# TOP.net
KiCad netlist of a schematic drawn in Altium Designer
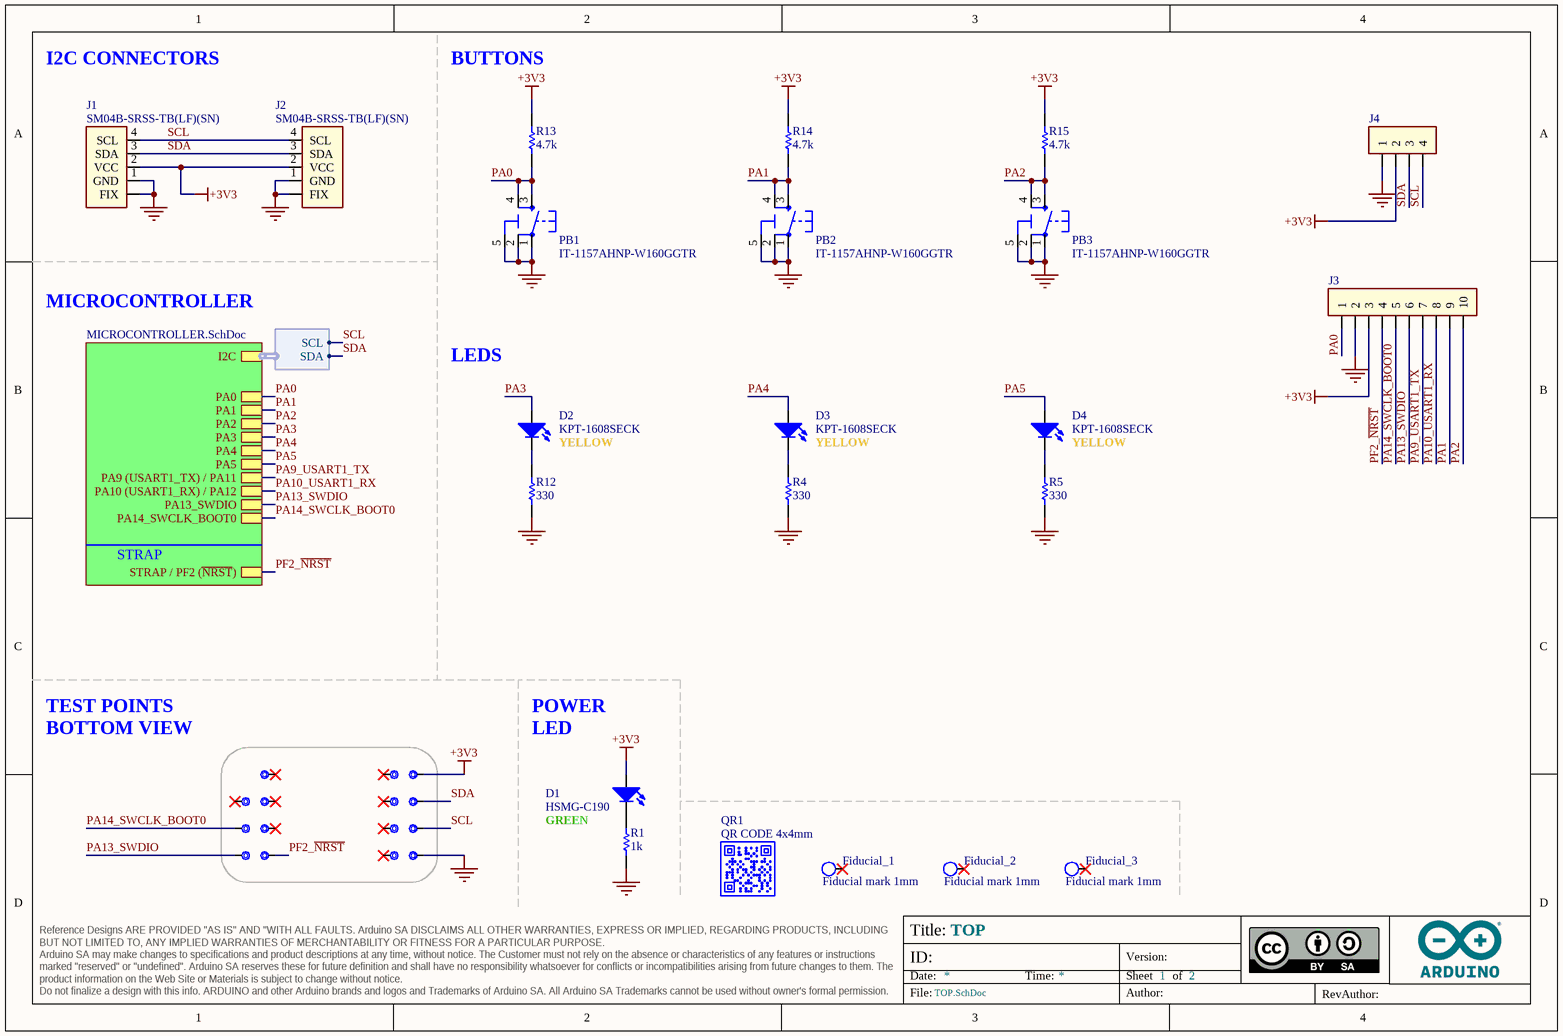
[diagram p0: TOP.SchDoc]

(export (version "E")
  (design (tool "Eeschema 10.0.6"))
  (components
    (comp (ref "3V3")
      (value "Test point 1.00mm")
      (footprint "TP-1.00MM")
      (fields (field (name "MANUFACTURER") "This is not a component"))
      (libsource (lib "Clean") (part "TESTPOINT"))
    )
    (comp (ref "D1")
      (value "HSMG-C190")
      (footprint "LEDC1608X80N-AK")
      (description "LED SMD 0603 GREEN/568 15mcd 120^")
      (fields (field (name "MANUFACTURER") "Broadcom"))
      (libsource (lib "Clean") (part "LED"))
    )
    (comp (ref "D2")
      (value "KPT-1608SECK")
      (footprint "LEDC1608X80N-AK")
      (description "LED SMD 0603 ORANGE601 250mcd 120^")
      (fields (field (name "MANUFACTURER") "Kingbright"))
      (libsource (lib "Clean") (part "LED"))
    )
    (comp (ref "D3")
      (value "KPT-1608SECK")
      (footprint "LEDC1608X80N-AK")
      (description "LED SMD 0603 ORANGE601 250mcd 120^")
      (fields (field (name "MANUFACTURER") "Kingbright"))
      (libsource (lib "Clean") (part "LED"))
    )
    (comp (ref "D4")
      (value "KPT-1608SECK")
      (footprint "LEDC1608X80N-AK")
      (description "LED SMD 0603 ORANGE601 250mcd 120^")
      (fields (field (name "MANUFACTURER") "Kingbright"))
      (libsource (lib "Clean") (part "LED"))
    )
    (comp (ref "Fiducial_1")
      (value "Fiducial mark 1mm")
      (footprint "Fiducial mark 1mm-Footprint-1")
      (description "Fiducial mark 1mm clearance 2mm")
      (libsource (lib "Clean") (part "Fiducial mark 1mm"))
    )
    (comp (ref "Fiducial_2")
      (value "Fiducial mark 1mm")
      (footprint "Fiducial mark 1mm-Footprint-1")
      (description "Fiducial mark 1mm clearance 2mm")
      (libsource (lib "Clean") (part "Fiducial mark 1mm"))
    )
    (comp (ref "Fiducial_3")
      (value "Fiducial mark 1mm")
      (footprint "Fiducial mark 1mm-Footprint-1")
      (description "Fiducial mark 1mm clearance 2mm")
      (libsource (lib "Clean") (part "Fiducial mark 1mm"))
    )
    (comp (ref "GND")
      (value "Test point 1.00mm")
      (footprint "TP-1.00MM")
      (fields (field (name "MANUFACTURER") "This is not a component"))
      (libsource (lib "Clean") (part "TESTPOINT"))
    )
    (comp (ref "J1")
      (value "SM04B-SRSS-TB(LF)(SN)")
      (footprint "SM04B-SRSS-TB(LF)(SN)-Footprint-1")
      (description "CONN JST 4POS SIDE 1MM TIN QWIIC")
      (fields (field (name "MANUFACTURER") "JST"))
      (libsource (lib "") (part "SM04B-SRSS-TB(LF)(SN)_1"))
    )
    (comp (ref "J2")
      (value "SM04B-SRSS-TB(LF)(SN)")
      (footprint "SM04B-SRSS-TB(LF)(SN)-Footprint-1")
      (description "CONN JST 4POS SIDE 1MM TIN QWIIC")
      (fields (field (name "MANUFACTURER") "JST"))
      (libsource (lib "Clean") (part "SM04B-SRSS-TB(LF)(SN)"))
    )
    (comp (ref "J3")
      (value "HEADER TH 2.54mm VERT. 1x010POS")
      (footprint "PIN HEADER 2.54mm VERT. 1x10POS")
      (libsource (lib "Clean") (part "PIN HEADER 2.54mm VERT. 1x10POS"))
    )
    (comp (ref "J4")
      (value "HEADER TH 2.54mm VERT. 1x004POS")
      (footprint "PIN HEADER 2.54mm VERT. 1x4POS-Footprint-1")
      (libsource (lib "Clean") (part "PIN HEADER 2.54mm VERT. 1x4POS"))
    )
    (comp (ref "NRST")
      (value "Test point 1.00mm")
      (footprint "TP-1.00MM")
      (fields (field (name "MANUFACTURER") "This is not a component"))
      (libsource (lib "Clean") (part "TESTPOINT"))
    )
    (comp (ref "PA6")
      (value "Test point 1.00mm")
      (footprint "TP-1.00MM")
      (fields (field (name "MANUFACTURER") "This is not a component"))
      (libsource (lib "Clean") (part "TESTPOINT"))
    )
    (comp (ref "PA7")
      (value "Test point 1.00mm")
      (footprint "TP-1.00MM")
      (fields (field (name "MANUFACTURER") "This is not a component"))
      (libsource (lib "Clean") (part "TESTPOINT"))
    )
    (comp (ref "PB1")
      (value "IT-1157AHNP-W160GGTR")
      (footprint "TS42")
      (description "PUSHBUTTON SMD 6x6 5 PINS")
      (fields (field (name "MANUFACTURER") "Switronic"))
      (libsource (lib "Clean") (part "IT-1157AHNP-W160GGTR"))
    )
    (comp (ref "PB2")
      (value "IT-1157AHNP-W160GGTR")
      (footprint "TS42")
      (description "PUSHBUTTON SMD 6x6 5 PINS")
      (fields (field (name "MANUFACTURER") "Switronic"))
      (libsource (lib "Clean") (part "IT-1157AHNP-W160GGTR"))
    )
    (comp (ref "PB3")
      (value "IT-1157AHNP-W160GGTR")
      (footprint "TS42")
      (description "PUSHBUTTON SMD 6x6 5 PINS")
      (fields (field (name "MANUFACTURER") "Switronic"))
      (libsource (lib "Clean") (part "IT-1157AHNP-W160GGTR"))
    )
    (comp (ref "PC14")
      (value "Test point 1.00mm")
      (footprint "TP-1.00MM")
      (fields (field (name "MANUFACTURER") "This is not a component"))
      (libsource (lib "Clean") (part "TESTPOINT"))
    )
    (comp (ref "PC15")
      (value "Test point 1.00mm")
      (footprint "TP-1.00MM")
      (fields (field (name "MANUFACTURER") "This is not a component"))
      (libsource (lib "Clean") (part "TESTPOINT"))
    )
    (comp (ref "QR1")
      (value "QR CODE 4x4mm")
      (footprint "QR CODE 4x4mm")
      (description "QR CODE 4x4mm on layer 34 (This is not a component)")
      (fields (field (name "PART NUMBER") "This is not a component"))
      (libsource (lib "Clean") (part "QR CODE 4x4mm"))
    )
    (comp (ref "R1")
      (value "1k")
      (footprint "RES-0402")
      (description "RES CHIP 0402 1k 1% 1/16W")
      (fields (field (name "PART NUMBER") "CRCW04021K00FKEDC") (field (name "TOLERANCE") "1%"))
      (libsource (lib "Clean") (part "RES"))
    )
    (comp (ref "R4")
      (value "330")
      (footprint "RES-0402")
      (description "RES CHIP 0402 330R 5% 1/16W")
      (fields (field (name "PART NUMBER") "CRCW0402330RJNED") (field (name "TOLERANCE") "5%"))
      (libsource (lib "Clean") (part "RES"))
    )
    (comp (ref "R5")
      (value "330")
      (footprint "RES-0402")
      (description "RES CHIP 0402 330R 5% 1/16W")
      (fields (field (name "PART NUMBER") "CRCW0402330RJNED") (field (name "TOLERANCE") "5%"))
      (libsource (lib "Clean") (part "RES"))
    )
    (comp (ref "R12")
      (value "330")
      (footprint "RES-0402")
      (description "RES CHIP 0402 330R 5% 1/16W")
      (fields (field (name "PART NUMBER") "CRCW0402330RJNED") (field (name "TOLERANCE") "5%"))
      (libsource (lib "Clean") (part "RES"))
    )
    (comp (ref "R13")
      (value "4.7k")
      (footprint "RES-0402")
      (description "RES CHIP 0402 4k7 1% 1/16W")
      (fields (field (name "PART NUMBER") "RC0402FR-074K7L") (field (name "TOLERANCE") "1%"))
      (libsource (lib "Clean") (part "RES"))
    )
    (comp (ref "R14")
      (value "4.7k")
      (footprint "RES-0402")
      (description "RES CHIP 0402 4k7 1% 1/16W")
      (fields (field (name "PART NUMBER") "RC0402FR-074K7L") (field (name "TOLERANCE") "1%"))
      (libsource (lib "Clean") (part "RES"))
    )
    (comp (ref "R15")
      (value "4.7k")
      (footprint "RES-0402")
      (description "RES CHIP 0402 4k7 1% 1/16W")
      (fields (field (name "PART NUMBER") "RC0402FR-074K7L") (field (name "TOLERANCE") "1%"))
      (libsource (lib "Clean") (part "RES"))
    )
    (comp (ref "SCL")
      (value "Test point 1.00mm")
      (footprint "TP-1.00MM")
      (fields (field (name "MANUFACTURER") "This is not a component"))
      (libsource (lib "Clean") (part "TESTPOINT"))
    )
    (comp (ref "SDA")
      (value "Test point 1.00mm")
      (footprint "TP-1.00MM")
      (fields (field (name "MANUFACTURER") "This is not a component"))
      (libsource (lib "Clean") (part "TESTPOINT"))
    )
    (comp (ref "SWCLK")
      (value "Test point 1.00mm")
      (footprint "TP-1.00MM")
      (fields (field (name "MANUFACTURER") "This is not a component"))
      (libsource (lib "Clean") (part "TESTPOINT"))
    )
    (comp (ref "SWDIO")
      (value "Test point 1.00mm")
      (footprint "TP-1.00MM")
      (fields (field (name "MANUFACTURER") "This is not a component"))
      (libsource (lib "Clean") (part "TESTPOINT"))
    )
    (comp (ref "TP9")
      (value "Test point 1.00mm")
      (footprint "TP-1.00MM")
      (fields (field (name "MANUFACTURER") "This is not a component"))
      (libsource (lib "Clean") (part "TESTPOINT"))
    )
    (comp (ref "TP10")
      (value "Test point 1.00mm")
      (footprint "TP-1.00MM")
      (fields (field (name "MANUFACTURER") "This is not a component"))
      (libsource (lib "Clean") (part "TESTPOINT"))
    )
    (comp (ref "TP11")
      (value "Test point 1.00mm")
      (footprint "TP-1.00MM")
      (fields (field (name "MANUFACTURER") "This is not a component"))
      (libsource (lib "Clean") (part "TESTPOINT"))
    )
    (comp (ref "TP12")
      (value "Test point 1.00mm")
      (footprint "TP-1.00MM")
      (fields (field (name "MANUFACTURER") "This is not a component"))
      (libsource (lib "Clean") (part "TESTPOINT"))
    )
  )
  (nets
    (net (code "2") (name "+3V3") (class "Default")
      (node (ref "3V3") (pin "X") (pinfunction "X_X") (pintype "passive"))
      (node (ref "D1") (pin "A") (pinfunction "A_A") (pintype "passive"))
      (node (ref "J1") (pin "2") (pinfunction "VCC_2") (pintype "passive"))
      (node (ref "J2") (pin "2") (pinfunction "VCC_2") (pintype "passive"))
      (node (ref "J3") (pin "3") (pinfunction "3_3") (pintype "passive"))
      (node (ref "J4") (pin "2") (pinfunction "2_2") (pintype "passive"))
      (node (ref "R13") (pin "2") (pinfunction "2_2") (pintype "passive"))
      (node (ref "R14") (pin "2") (pinfunction "2_2") (pintype "passive"))
      (node (ref "R15") (pin "2") (pinfunction "2_2") (pintype "passive"))
    )
    (net (code "3") (name "/PA0") (class "Default")
      (node (ref "J3") (pin "1") (pinfunction "1_1") (pintype "passive"))
      (node (ref "PB1") (pin "3") (pinfunction "3_3") (pintype "passive"))
      (node (ref "PB1") (pin "4") (pinfunction "4_4") (pintype "passive"))
      (node (ref "R13") (pin "1") (pinfunction "1_1") (pintype "passive"))
    )
    (net (code "4") (name "/PA1") (class "Default")
      (node (ref "J3") (pin "9") (pinfunction "9_9") (pintype "passive"))
      (node (ref "PB2") (pin "3") (pinfunction "3_3") (pintype "passive"))
      (node (ref "PB2") (pin "4") (pinfunction "4_4") (pintype "passive"))
      (node (ref "R14") (pin "1") (pinfunction "1_1") (pintype "passive"))
    )
    (net (code "5") (name "/PA2") (class "Default")
      (node (ref "J3") (pin "10") (pinfunction "10_10") (pintype "passive"))
      (node (ref "PB3") (pin "3") (pinfunction "3_3") (pintype "passive"))
      (node (ref "PB3") (pin "4") (pinfunction "4_4") (pintype "passive"))
      (node (ref "R15") (pin "1") (pinfunction "1_1") (pintype "passive"))
    )
    (net (code "6") (name "/PA3") (class "Default")
      (node (ref "D2") (pin "A") (pinfunction "A_A") (pintype "passive"))
    )
    (net (code "7") (name "/PA4") (class "Default")
      (node (ref "D3") (pin "A") (pinfunction "A_A") (pintype "passive"))
    )
    (net (code "8") (name "/PA5") (class "Default")
      (node (ref "D4") (pin "A") (pinfunction "A_A") (pintype "passive"))
    )
    (net (code "9") (name "/PA9_USART1_TX") (class "Default")
      (node (ref "J3") (pin "7") (pinfunction "7_7") (pintype "passive"))
    )
    (net (code "10") (name "/PA10_USART1_RX") (class "Default")
      (node (ref "J3") (pin "8") (pinfunction "8_8") (pintype "passive"))
    )
    (net (code "11") (name "/PA13_SWDIO") (class "Default")
      (node (ref "J3") (pin "6") (pinfunction "6_6") (pintype "passive"))
      (node (ref "SWCLK") (pin "X") (pinfunction "X_X") (pintype "passive"))
    )
    (net (code "12") (name "/PA14_SWCLK_BOOT0") (class "Default")
      (node (ref "J3") (pin "5") (pinfunction "5_5") (pintype "passive"))
      (node (ref "SWDIO") (pin "X") (pinfunction "X_X") (pintype "passive"))
    )
    (net (code "13") (name "/PF2_~{NRST}") (class "Default")
      (node (ref "J3") (pin "4") (pinfunction "4_4") (pintype "passive"))
      (node (ref "NRST") (pin "X") (pinfunction "X_X") (pintype "passive"))
    )
    (net (code "14") (name "/SCL") (class "Default")
      (node (ref "J1") (pin "4") (pinfunction "SCL_4") (pintype "passive"))
      (node (ref "J2") (pin "4") (pinfunction "SCL_4") (pintype "passive"))
      (node (ref "J4") (pin "4") (pinfunction "4_4") (pintype "passive"))
      (node (ref "SCL") (pin "X") (pinfunction "X_X") (pintype "passive"))
    )
    (net (code "15") (name "/SDA") (class "Default")
      (node (ref "J1") (pin "3") (pinfunction "SDA_3") (pintype "passive"))
      (node (ref "J2") (pin "3") (pinfunction "SDA_3") (pintype "passive"))
      (node (ref "J4") (pin "3") (pinfunction "3_3") (pintype "passive"))
      (node (ref "SDA") (pin "X") (pinfunction "X_X") (pintype "passive"))
    )
    (net (code "17") (name "GND") (class "Default")
      (node (ref "GND") (pin "X") (pinfunction "X_X") (pintype "passive"))
      (node (ref "J1") (pin "1") (pinfunction "GND_1") (pintype "passive"))
      (node (ref "J1") (pin "FIX") (pinfunction "FIX_FIX") (pintype "passive"))
      (node (ref "J2") (pin "1") (pinfunction "GND_1") (pintype "passive"))
      (node (ref "J2") (pin "FIX") (pinfunction "FIX_FIX") (pintype "passive"))
      (node (ref "J3") (pin "2") (pinfunction "2_2") (pintype "passive"))
      (node (ref "J4") (pin "1") (pinfunction "1_1") (pintype "passive"))
      (node (ref "PB1") (pin "1") (pinfunction "1_1") (pintype "passive"))
      (node (ref "PB1") (pin "2") (pinfunction "2_2") (pintype "passive"))
      (node (ref "PB1") (pin "5") (pinfunction "5-GND_5") (pintype "power_in"))
      (node (ref "PB2") (pin "1") (pinfunction "1_1") (pintype "passive"))
      (node (ref "PB2") (pin "2") (pinfunction "2_2") (pintype "passive"))
      (node (ref "PB2") (pin "5") (pinfunction "5-GND_5") (pintype "power_in"))
      (node (ref "PB3") (pin "1") (pinfunction "1_1") (pintype "passive"))
      (node (ref "PB3") (pin "2") (pinfunction "2_2") (pintype "passive"))
      (node (ref "PB3") (pin "5") (pinfunction "5-GND_5") (pintype "power_in"))
      (node (ref "R1") (pin "1") (pinfunction "1_1") (pintype "passive"))
      (node (ref "R12") (pin "1") (pinfunction "1_1") (pintype "passive"))
      (node (ref "R4") (pin "1") (pinfunction "1_1") (pintype "passive"))
      (node (ref "R5") (pin "1") (pinfunction "1_1") (pintype "passive"))
    )
    (net (code "18") (name "Net-(D1-PadC)") (class "Default")
      (node (ref "D1") (pin "C") (pinfunction "C_C") (pintype "passive"))
      (node (ref "R1") (pin "2") (pinfunction "2_2") (pintype "passive"))
    )
    (net (code "19") (name "Net-(D2-PadC)") (class "Default")
      (node (ref "D2") (pin "C") (pinfunction "C_C") (pintype "passive"))
      (node (ref "R12") (pin "2") (pinfunction "2_2") (pintype "passive"))
    )
    (net (code "20") (name "Net-(D3-PadC)") (class "Default")
      (node (ref "D3") (pin "C") (pinfunction "C_C") (pintype "passive"))
      (node (ref "R4") (pin "2") (pinfunction "2_2") (pintype "passive"))
    )
    (net (code "21") (name "Net-(D4-PadC)") (class "Default")
      (node (ref "D4") (pin "C") (pinfunction "C_C") (pintype "passive"))
      (node (ref "R5") (pin "2") (pinfunction "2_2") (pintype "passive"))
    )
    (net (code "22") (name "unconnected-(Fiducial_1-Pad1)") (class "Default")
      (node (ref "Fiducial_1") (pin "1") (pinfunction "1_1") (pintype "passive+no_connect"))
    )
    (net (code "23") (name "unconnected-(Fiducial_2-Pad1)") (class "Default")
      (node (ref "Fiducial_2") (pin "1") (pinfunction "1_1") (pintype "passive+no_connect"))
    )
    (net (code "24") (name "unconnected-(Fiducial_3-Pad1)") (class "Default")
      (node (ref "Fiducial_3") (pin "1") (pinfunction "1_1") (pintype "passive+no_connect"))
    )
    (net (code "25") (name "unconnected-(PA6-PadX)") (class "Default")
      (node (ref "PA6") (pin "X") (pinfunction "X_X") (pintype "passive+no_connect"))
    )
    (net (code "26") (name "unconnected-(PA7-PadX)") (class "Default")
      (node (ref "PA7") (pin "X") (pinfunction "X_X") (pintype "passive+no_connect"))
    )
    (net (code "27") (name "unconnected-(PC14-PadX)") (class "Default")
      (node (ref "PC14") (pin "X") (pinfunction "X_X") (pintype "passive+no_connect"))
    )
    (net (code "28") (name "unconnected-(PC15-PadX)") (class "Default")
      (node (ref "PC15") (pin "X") (pinfunction "X_X") (pintype "passive+no_connect"))
    )
    (net (code "29") (name "unconnected-(TP9-PadX)") (class "Default")
      (node (ref "TP9") (pin "X") (pinfunction "X_X") (pintype "passive+no_connect"))
    )
    (net (code "30") (name "unconnected-(TP10-PadX)") (class "Default")
      (node (ref "TP10") (pin "X") (pinfunction "X_X") (pintype "passive+no_connect"))
    )
    (net (code "31") (name "unconnected-(TP11-PadX)") (class "Default")
      (node (ref "TP11") (pin "X") (pinfunction "X_X") (pintype "passive+no_connect"))
    )
    (net (code "32") (name "unconnected-(TP12-PadX)") (class "Default")
      (node (ref "TP12") (pin "X") (pinfunction "X_X") (pintype "passive+no_connect"))
    )
  )
)
